# flyback.net
KiCad netlist of a schematic drawn in Altium Designer
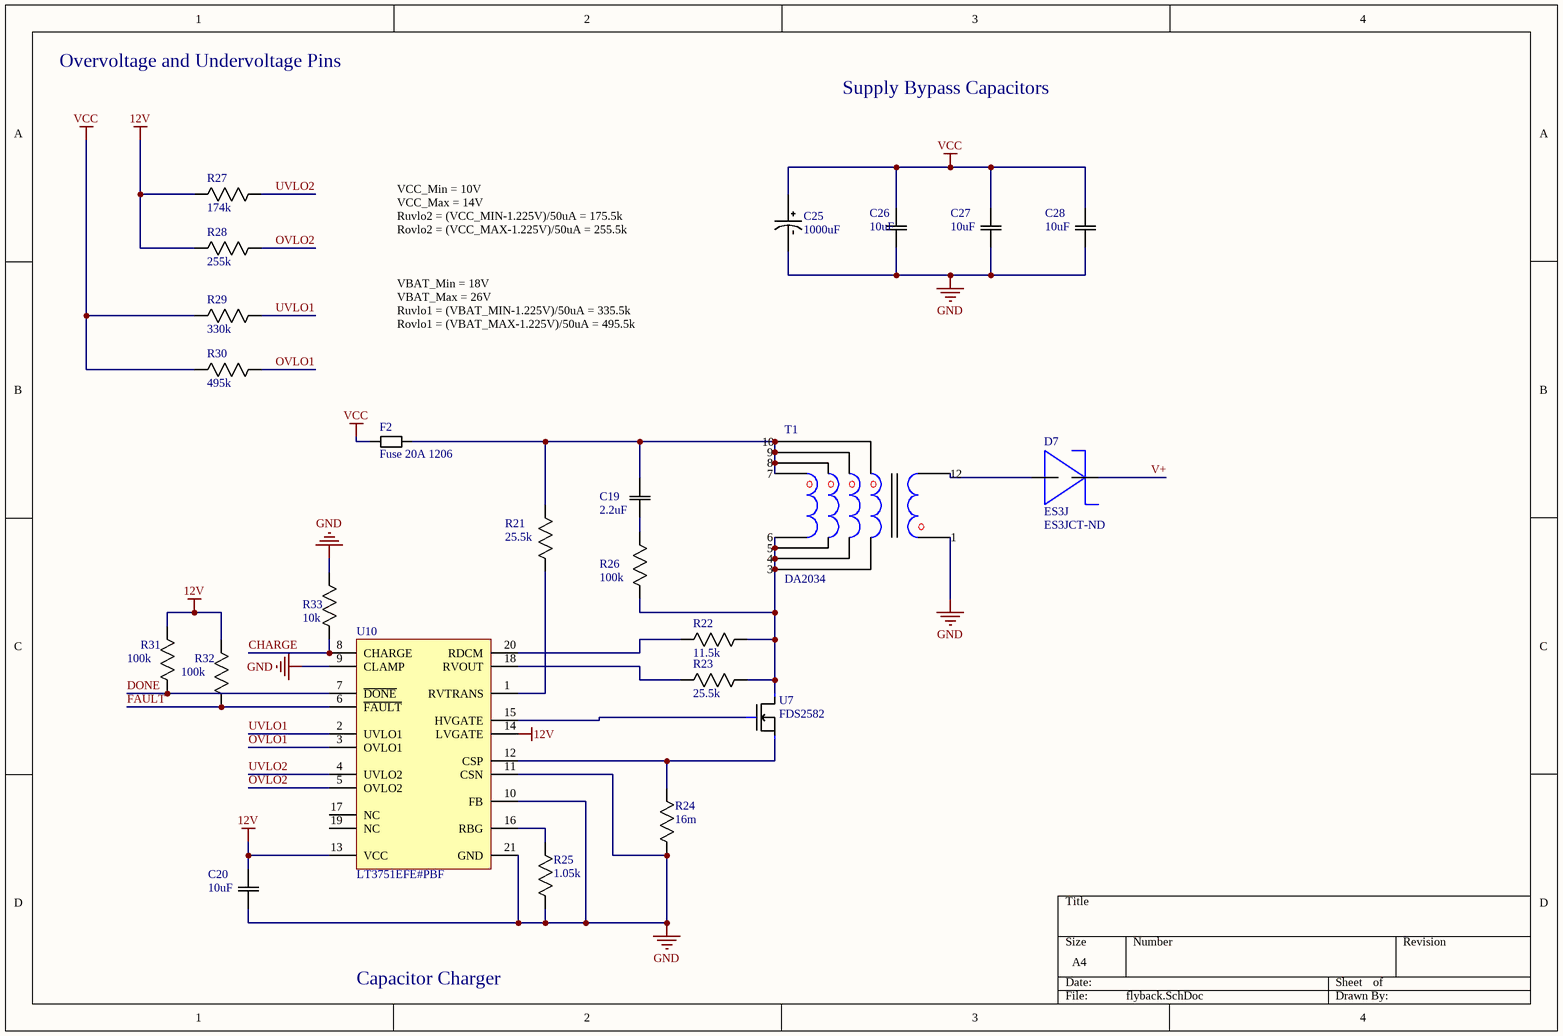
[diagram p0: flyback.SchDoc]

(export (version "E")
  (design (tool "Eeschema 10.0.6"))
  (components
    (comp (ref "C19")
      (value "2.2uF")
      (footprint "0805")
      (description "CAP CER 1UF 50V X7R 0805")
      (fields (field (name "MP") "C0805C225K4RACTU") (field (name "MF") "KEMET"))
      (libsource (lib "AltiumLibraries") (part "CAP 2.2uF 0805"))
    )
    (comp (ref "C20")
      (value "10uF")
      (footprint "0805")
      (description "CAP CER 10UF 10V X5R 0805")
      (fields (field (name "MP") "C0805C106K8PACTU") (field (name "MF") "KEMET"))
      (libsource (lib "AltiumLibraries") (part "CAP 10uF 0805"))
    )
    (comp (ref "C25")
      (value "1000uF")
      (footprint "CAP POL 1000uF THRU")
      (description "NICHICON   UVR1E102MPD1TD   ALUMINUM ELECTROLYTIC CAPACITOR, 1000UF, 25V, 20%, RADIAL, FULL REEL")
      (fields
        (field (name "MANUFACTURER") "Nichicon")
        (field (name "MANUFACTURER PART NUMBER") "UVR1E102MPD1TD")
      )
      (libsource (lib "AltiumLibraries") (part "CAP POL 1000uF THRU"))
    )
    (comp (ref "C26")
      (value "10uF")
      (footprint "0805")
      (description "CAP CER 10UF 10V X5R 0805")
      (fields (field (name "MP") "C0805C106K8PACTU") (field (name "MF") "KEMET"))
      (libsource (lib "AltiumLibraries") (part "CAP 10uF 0805"))
    )
    (comp (ref "C27")
      (value "10uF")
      (footprint "0805")
      (description "CAP CER 10UF 10V X5R 0805")
      (fields (field (name "MP") "C0805C106K8PACTU") (field (name "MF") "KEMET"))
      (libsource (lib "AltiumLibraries") (part "CAP 10uF 0805"))
    )
    (comp (ref "C28")
      (value "10uF")
      (footprint "0805")
      (description "CAP CER 10UF 10V X5R 0805")
      (fields (field (name "MP") "C0805C106K8PACTU") (field (name "MF") "KEMET"))
      (libsource (lib "AltiumLibraries") (part "CAP 10uF 0805"))
    )
    (comp (ref "D7")
      (value "ES3J")
      (footprint "D0214-AB")
      (description "Diode Switching 600V 3A 2-Pin DO-214AB T/R")
      (fields
        (field (name "MANUFACTURER") "ON Semiconductor / Fairchild")
        (field (name "VOLTAGE") "600V")
        (field (name "SUPPLIER PART NUMBER 1") "ES3JCT-ND")
      )
      (libsource (lib "AltiumLibraries") (part "ES3J"))
    )
    (comp (ref "F2")
      (value "Fuse 20A 1206")
      (footprint "1206")
      (description "FUSE 20A 32V AC 63V DC 1206")
      (libsource (lib "AltiumLibraries") (part "FUSE 20A 63V SLOW"))
    )
    (comp (ref "R21")
      (value "25.5k")
      (footprint "0805")
      (description "0805 Resistor, 6A, 0.125W, 25ppm, 0.1%, 25K5")
      (fields
        (field (name "MANUFACTURER") "Panasonic")
        (field (name "MANUFACTURER PART NUMBER") "ERA-6AEB2552V")
      )
      (libsource (lib "AltiumLibraries") (part "RES 25.5k 0805"))
    )
    (comp (ref "R22")
      (value "11.5k")
      (footprint "0805")
      (description "Res Thin Film 0805 11.5K Ohm 0.1% 1/8W 25ppm/C Molded SMD SMD Punched Carrier T/R")
      (fields
        (field (name "MANUFACTURER") "Panasonic")
        (field (name "MANUFACTURER PART NUMBER") "ERA-6AEB1152V")
      )
      (libsource (lib "AltiumLibraries") (part "RES 11.5k 0805"))
    )
    (comp (ref "R23")
      (value "25.5k")
      (footprint "0805")
      (description "0805 Resistor, 6A, 0.125W, 25ppm, 0.1%, 25K5")
      (fields
        (field (name "MANUFACTURER") "Panasonic")
        (field (name "MANUFACTURER PART NUMBER") "ERA-6AEB2552V")
      )
      (libsource (lib "") (part "RES 25.5k 0805_1"))
    )
    (comp (ref "R24")
      (value "16m")
      (footprint "0805")
      (description "Res Thick Film 0805 0.016 Ohm 1% 0.5W(1/2W) ±200ppm/C Molded SMD Automotive Punched T/R")
      (fields
        (field (name "MANUFACTURER") "Panasonic")
        (field (name "MANUFACTURER PART NUMBER") "ERJ-6BWFR016V")
      )
      (libsource (lib "AltiumLibraries") (part "RES 16mOhm 0805"))
    )
    (comp (ref "R25")
      (value "1.05k")
      (footprint "0805")
      (description "Res Thin Film 0805 10.5K Ohm 0.1% 0.125W(1/8W) ±25ppm/C Molded SMD Automotive Punched T/R")
      (fields
        (field (name "MANUFACTURER") "Panasonic")
        (field (name "MANUFACTURER PART NUMBER") "ERA-6AEB1052V")
      )
      (libsource (lib "AltiumLibraries") (part "RES 1.05k 0805"))
    )
    (comp (ref "R26")
      (value "100k")
      (footprint "0805")
      (description "RES SMD 100K OHM 1% 1/8W 0805")
      (fields (field (name "MP") "RC0805FR-07100KL") (field (name "MF") "Yageo"))
      (libsource (lib "AltiumLibraries") (part "RES 100k 0805"))
    )
    (comp (ref "R27")
      (value "174k")
      (footprint "0805")
      (description "RES SMD 174K OHM 1% 1/8W 0805")
      (fields
        (field (name "MANUFACTURER") "Yageo")
        (field (name "MANUFACTURER PART NUMBER") "RC0805FR-07174KL")
      )
      (libsource (lib "AltiumLibraries") (part "RES 174k 0805"))
    )
    (comp (ref "R28")
      (value "255k")
      (footprint "0805")
      (description "0805 Resistor, 6A, 0.125W, 25ppm, 0.1%, 255K")
      (fields
        (field (name "MANUFACTURER") "Panasonic")
        (field (name "MANUFACTURER PART NUMBER") "ERA-6AEB2553V")
      )
      (libsource (lib "AltiumLibraries") (part "RES 255k 0805"))
    )
    (comp (ref "R29")
      (value "330k")
      (footprint "0805")
      (description "RES SMD 274K OHM 1% 1/8W 0805")
      (libsource (lib "AltiumLibraries") (part "RES 330k 0805"))
    )
    (comp (ref "R30")
      (value "495k")
      (footprint "0805")
      (description "RES SMD 499K OHM 1% 1/8W 0805")
      (fields
        (field (name "MANUFACTURER") "Yageo")
        (field (name "MANUFACTURER PART NUMBER") "RC0805FR-07499KL")
      )
      (libsource (lib "AltiumLibraries") (part "RES 495k 0805"))
    )
    (comp (ref "R31")
      (value "100k")
      (footprint "0805")
      (description "RES SMD 100K OHM 1% 1/8W 0805")
      (fields (field (name "MP") "RC0805FR-07100KL") (field (name "MF") "Yageo"))
      (libsource (lib "") (part "RES 100k 0805_1"))
    )
    (comp (ref "R32")
      (value "100k")
      (footprint "0805")
      (description "RES SMD 100K OHM 1% 1/8W 0805")
      (fields (field (name "MP") "RC0805FR-07100KL") (field (name "MF") "Yageo"))
      (libsource (lib "") (part "RES 100k 0805_1"))
    )
    (comp (ref "R33")
      (value "10k")
      (footprint "0805")
      (description "RES SMD 10K OHM 1% 1/8W 0805")
      (fields (field (name "TOLERANCE") "1%"))
      (libsource (lib "AltiumLibraries") (part "RES 10k 1/8W"))
    )
    (comp (ref "T1")
      (value "DA2034")
      (footprint "DA2034")
      (description "Audio Transformers / Signal Transformers DA2032 Cap Chrgr For Linear LT3750/51")
      (libsource (lib "AltiumLibraries") (part "DA2034"))
    )
    (comp (ref "U7")
      (value "FDS2582")
      (footprint "8-SOIC MOSFET")
      (description "N-Channel 150V 4.1A (Ta) 2.5W (Ta) Surface Mount 8-SOIC")
      (fields (field (name "MF") "ON Semiconductor"))
      (libsource (lib "AltiumLibraries") (part "FDS2582"))
    )
    (comp (ref "U10")
      (value "LT3751EFE#PBF")
      (footprint "LT-FE-20-EPV-CB_L")
      (description "Controller to 20-Pin TSSOP EP")
      (fields (field (name "MANUFACTURER") "Analog Devices / Linear Technology"))
      (libsource (lib "AltiumLibraries") (part "LT3751EFE#PBF"))
    )
  )
  (nets
    (net (code "1") (name "/CHARGE") (class "Default")
      (node (ref "R33") (pin "2") (pinfunction "R2_2") (pintype "passive"))
      (node (ref "U10") (pin "8") (pinfunction "CHARGE_8") (pintype "passive"))
    )
    (net (code "2") (name "/DONE") (class "Default")
      (node (ref "R31") (pin "1") (pinfunction "R1_1") (pintype "passive"))
      (node (ref "U10") (pin "7") (pinfunction "~{DONE}_7") (pintype "passive"))
    )
    (net (code "3") (name "/FAULT") (class "Default")
      (node (ref "R32") (pin "1") (pinfunction "R1_1") (pintype "passive"))
      (node (ref "U10") (pin "6") (pinfunction "~{FAULT}_6") (pintype "passive"))
    )
    (net (code "4") (name "/OVLO1") (class "Default")
      (node (ref "R30") (pin "1") (pinfunction "R1_1") (pintype "passive"))
      (node (ref "U10") (pin "3") (pinfunction "OVLO1_3") (pintype "passive"))
    )
    (net (code "5") (name "/OVLO2") (class "Default")
      (node (ref "R28") (pin "1") (pinfunction "R1_1") (pintype "passive"))
      (node (ref "U10") (pin "5") (pinfunction "OVLO2_5") (pintype "passive"))
    )
    (net (code "6") (name "/UVLO1") (class "Default")
      (node (ref "R29") (pin "1") (pinfunction "R1_1") (pintype "passive"))
      (node (ref "U10") (pin "2") (pinfunction "UVLO1_2") (pintype "passive"))
    )
    (net (code "7") (name "/UVLO2") (class "Default")
      (node (ref "R27") (pin "1") (pinfunction "R1_1") (pintype "passive"))
      (node (ref "U10") (pin "4") (pinfunction "UVLO2_4") (pintype "passive"))
    )
    (net (code "8") (name "/V+") (class "Default")
      (node (ref "D7") (pin "OUT") (pinfunction "OUT_OUT") (pintype "passive"))
    )
    (net (code "9") (name "12V") (class "Default")
      (node (ref "C20") (pin "1") (pinfunction "C1_1") (pintype "passive"))
      (node (ref "R27") (pin "2") (pinfunction "R2_2") (pintype "passive"))
      (node (ref "R28") (pin "2") (pinfunction "R2_2") (pintype "passive"))
      (node (ref "R31") (pin "2") (pinfunction "R2_2") (pintype "passive"))
      (node (ref "R32") (pin "2") (pinfunction "R2_2") (pintype "passive"))
      (node (ref "U10") (pin "13") (pinfunction "VCC_13") (pintype "passive"))
      (node (ref "U10") (pin "14") (pinfunction "LVGATE_14") (pintype "passive"))
    )
    (net (code "10") (name "GND") (class "Default")
      (node (ref "C20") (pin "2") (pinfunction "C2_2") (pintype "passive"))
      (node (ref "C25") (pin "NEG") (pinfunction "NEG_NEG") (pintype "passive"))
      (node (ref "C26") (pin "2") (pinfunction "C2_2") (pintype "passive"))
      (node (ref "C27") (pin "2") (pinfunction "C2_2") (pintype "passive"))
      (node (ref "C28") (pin "2") (pinfunction "C2_2") (pintype "passive"))
      (node (ref "R24") (pin "2") (pinfunction "R2_2") (pintype "passive"))
      (node (ref "R25") (pin "2") (pinfunction "R2_2") (pintype "passive"))
      (node (ref "R33") (pin "1") (pinfunction "R1_1") (pintype "passive"))
      (node (ref "T1") (pin "1") (pinfunction "1_1") (pintype "passive"))
      (node (ref "U10") (pin "10") (pinfunction "FB_10") (pintype "passive"))
      (node (ref "U10") (pin "11") (pinfunction "CSN_11") (pintype "passive"))
      (node (ref "U10") (pin "21") (pinfunction "GND_21") (pintype "passive"))
      (node (ref "U10") (pin "9") (pinfunction "CLAMP_9") (pintype "passive"))
    )
    (net (code "11") (name "Net-(C19-C1)") (class "Default")
      (node (ref "C19") (pin "1") (pinfunction "C1_1") (pintype "passive"))
      (node (ref "R26") (pin "1") (pinfunction "R1_1") (pintype "passive"))
    )
    (net (code "12") (name "Net-(C19-C2)") (class "Default")
      (node (ref "C19") (pin "2") (pinfunction "C2_2") (pintype "passive"))
      (node (ref "F2") (pin "2") (pinfunction "2_2") (pintype "passive"))
      (node (ref "R21") (pin "1") (pinfunction "R1_1") (pintype "passive"))
      (node (ref "T1") (pin "10") (pinfunction "10_10") (pintype "passive"))
      (node (ref "T1") (pin "7") (pinfunction "7_7") (pintype "passive"))
      (node (ref "T1") (pin "8") (pinfunction "8_8") (pintype "passive"))
      (node (ref "T1") (pin "9") (pinfunction "9_9") (pintype "passive"))
    )
    (net (code "13") (name "Net-(D7-PadIN)") (class "Default")
      (node (ref "D7") (pin "IN") (pinfunction "IN_IN") (pintype "passive"))
      (node (ref "T1") (pin "12") (pinfunction "12_12") (pintype "passive"))
    )
    (net (code "14") (name "Net-(R21-R2)") (class "Default")
      (node (ref "R21") (pin "2") (pinfunction "R2_2") (pintype "passive"))
      (node (ref "U10") (pin "1") (pinfunction "RVTRANS_1") (pintype "passive"))
    )
    (net (code "15") (name "Net-(R22-R1)") (class "Default")
      (node (ref "R22") (pin "1") (pinfunction "R1_1") (pintype "passive"))
      (node (ref "R23") (pin "1") (pinfunction "R1_1") (pintype "passive"))
      (node (ref "R26") (pin "2") (pinfunction "R2_2") (pintype "passive"))
      (node (ref "T1") (pin "3") (pinfunction "3_3") (pintype "passive"))
      (node (ref "T1") (pin "4") (pinfunction "4_4") (pintype "passive"))
      (node (ref "T1") (pin "5") (pinfunction "5_5") (pintype "passive"))
      (node (ref "T1") (pin "6") (pinfunction "6_6") (pintype "passive"))
      (node (ref "U7") (pin "D") (pinfunction "D_D") (pintype "passive"))
    )
    (net (code "16") (name "Net-(R22-R2)") (class "Default")
      (node (ref "R22") (pin "2") (pinfunction "R2_2") (pintype "passive"))
      (node (ref "U10") (pin "20") (pinfunction "RDCM_20") (pintype "passive"))
    )
    (net (code "17") (name "Net-(R23-R2)") (class "Default")
      (node (ref "R23") (pin "2") (pinfunction "R2_2") (pintype "passive"))
      (node (ref "U10") (pin "18") (pinfunction "RVOUT_18") (pintype "passive"))
    )
    (net (code "18") (name "Net-(R24-R1)") (class "Default")
      (node (ref "R24") (pin "1") (pinfunction "R1_1") (pintype "passive"))
      (node (ref "U10") (pin "12") (pinfunction "CSP_12") (pintype "passive"))
      (node (ref "U7") (pin "S") (pinfunction "S_S") (pintype "passive"))
    )
    (net (code "19") (name "Net-(R25-R1)") (class "Default")
      (node (ref "R25") (pin "1") (pinfunction "R1_1") (pintype "passive"))
      (node (ref "U10") (pin "16") (pinfunction "RBG_16") (pintype "passive"))
    )
    (net (code "20") (name "Net-(U10-HVGATE)") (class "Default")
      (node (ref "U10") (pin "15") (pinfunction "HVGATE_15") (pintype "passive"))
      (node (ref "U7") (pin "G") (pinfunction "G_G") (pintype "passive"))
    )
    (net (code "21") (name "VCC") (class "Default")
      (node (ref "C25") (pin "POS") (pinfunction "POS_POS") (pintype "passive"))
      (node (ref "C26") (pin "1") (pinfunction "C1_1") (pintype "passive"))
      (node (ref "C27") (pin "1") (pinfunction "C1_1") (pintype "passive"))
      (node (ref "C28") (pin "1") (pinfunction "C1_1") (pintype "passive"))
      (node (ref "F2") (pin "1") (pinfunction "1_1") (pintype "passive"))
      (node (ref "R29") (pin "2") (pinfunction "R2_2") (pintype "passive"))
      (node (ref "R30") (pin "2") (pinfunction "R2_2") (pintype "passive"))
    )
    (net (code "22") (name "unconnected-(U10-NC-Pad17)") (class "Default")
      (node (ref "U10") (pin "17") (pinfunction "NC_17") (pintype "passive"))
    )
    (net (code "23") (name "unconnected-(U10-NC-Pad19)") (class "Default")
      (node (ref "U10") (pin "19") (pinfunction "NC_19") (pintype "passive"))
    )
  )
)
